# new_reg.net
KiCad netlist of a schematic drawn in EAGLE
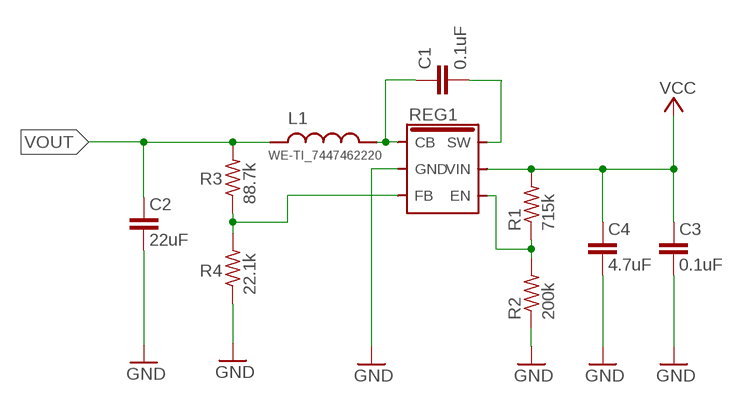
[diagram p0: schematic, sheet 1]

(export (version "E")
  (design (tool "Eeschema 10.0.6"))
  (components
    (comp (ref "C1")
      (value "0.1uF")
      (footprint "eagle-import:C0603")
      (libsource (lib "eagle-import") (part "C-EUC0603"))
    )
    (comp (ref "C2")
      (value "22uF")
      (footprint "eagle-import:C0603")
      (libsource (lib "eagle-import") (part "C-EUC0603"))
    )
    (comp (ref "C3")
      (value "0.1uF")
      (footprint "eagle-import:C0603")
      (libsource (lib "eagle-import") (part "C-EUC0603"))
    )
    (comp (ref "C4")
      (value "4.7uF")
      (footprint "eagle-import:C0603")
      (libsource (lib "eagle-import") (part "C-EUC0603"))
    )
    (comp (ref "L1")
      (value "WE-TI_7447462220")
      (footprint "eagle-import:WE-TI_5075")
      (libsource (lib "eagle-import") (part "WE-TI_7447462220"))
    )
    (comp (ref "R1")
      (value "715k")
      (footprint "eagle-import:R0603")
      (libsource (lib "eagle-import") (part "R-US_R0603"))
    )
    (comp (ref "R2")
      (value "200k")
      (footprint "eagle-import:R0603")
      (libsource (lib "eagle-import") (part "R-US_R0603"))
    )
    (comp (ref "R3")
      (value "88.7k")
      (footprint "eagle-import:R0603")
      (libsource (lib "eagle-import") (part "R-US_R0603"))
    )
    (comp (ref "R4")
      (value "22.1k")
      (footprint "eagle-import:R0603")
      (libsource (lib "eagle-import") (part "R-US_R0603"))
    )
    (comp (ref "REG1")
      (value "LMR50410")
      (footprint "eagle-import:SOT-23-6")
      (libsource (lib "eagle-import") (part "LMR50410"))
    )
  )
  (nets
    (net (code "1") (name "GND") (class "Default")
      (node (ref "C2") (pin "2") (pinfunction "2_2") (pintype "passive"))
      (node (ref "C3") (pin "2") (pinfunction "2_2") (pintype "passive"))
      (node (ref "C4") (pin "2") (pinfunction "2_2") (pintype "passive"))
      (node (ref "R2") (pin "1") (pinfunction "1_1") (pintype "passive"))
      (node (ref "R4") (pin "1") (pinfunction "1_1") (pintype "passive"))
      (node (ref "REG1") (pin "P$2") (pinfunction "GND_P$2") (pintype "bidirectional"))
    )
    (net (code "2") (name "Net-(REG1-CB)") (class "Default")
      (node (ref "C1") (pin "1") (pinfunction "1_1") (pintype "passive"))
      (node (ref "L1") (pin "P$2") (pinfunction "P$2_P$2") (pintype "bidirectional"))
      (node (ref "REG1") (pin "P$1") (pinfunction "CB_P$1") (pintype "bidirectional"))
    )
    (net (code "3") (name "Net-(REG1-EN)") (class "Default")
      (node (ref "R1") (pin "1") (pinfunction "1_1") (pintype "passive"))
      (node (ref "R2") (pin "2") (pinfunction "2_2") (pintype "passive"))
      (node (ref "REG1") (pin "P$4") (pinfunction "EN_P$4") (pintype "bidirectional"))
    )
    (net (code "4") (name "Net-(REG1-FB)") (class "Default")
      (node (ref "R3") (pin "1") (pinfunction "1_1") (pintype "passive"))
      (node (ref "R4") (pin "2") (pinfunction "2_2") (pintype "passive"))
      (node (ref "REG1") (pin "P$3") (pinfunction "FB_P$3") (pintype "bidirectional"))
    )
    (net (code "5") (name "Net-(REG1-SW)") (class "Default")
      (node (ref "C1") (pin "2") (pinfunction "2_2") (pintype "passive"))
      (node (ref "REG1") (pin "P$6") (pinfunction "SW_P$6") (pintype "bidirectional"))
    )
    (net (code "6") (name "VCC") (class "Default")
      (node (ref "C3") (pin "1") (pinfunction "1_1") (pintype "passive"))
      (node (ref "C4") (pin "1") (pinfunction "1_1") (pintype "passive"))
      (node (ref "R1") (pin "2") (pinfunction "2_2") (pintype "passive"))
      (node (ref "REG1") (pin "P$5") (pinfunction "VIN_P$5") (pintype "bidirectional"))
    )
    (net (code "7") (name "VOUT") (class "Default")
      (node (ref "C2") (pin "1") (pinfunction "1_1") (pintype "passive"))
      (node (ref "L1") (pin "P$1") (pinfunction "P$1_P$1") (pintype "bidirectional"))
      (node (ref "R3") (pin "2") (pinfunction "2_2") (pintype "passive"))
    )
  )
)
